# Analog_Greippi.net
KiCad netlist of a schematic drawn in EAGLE
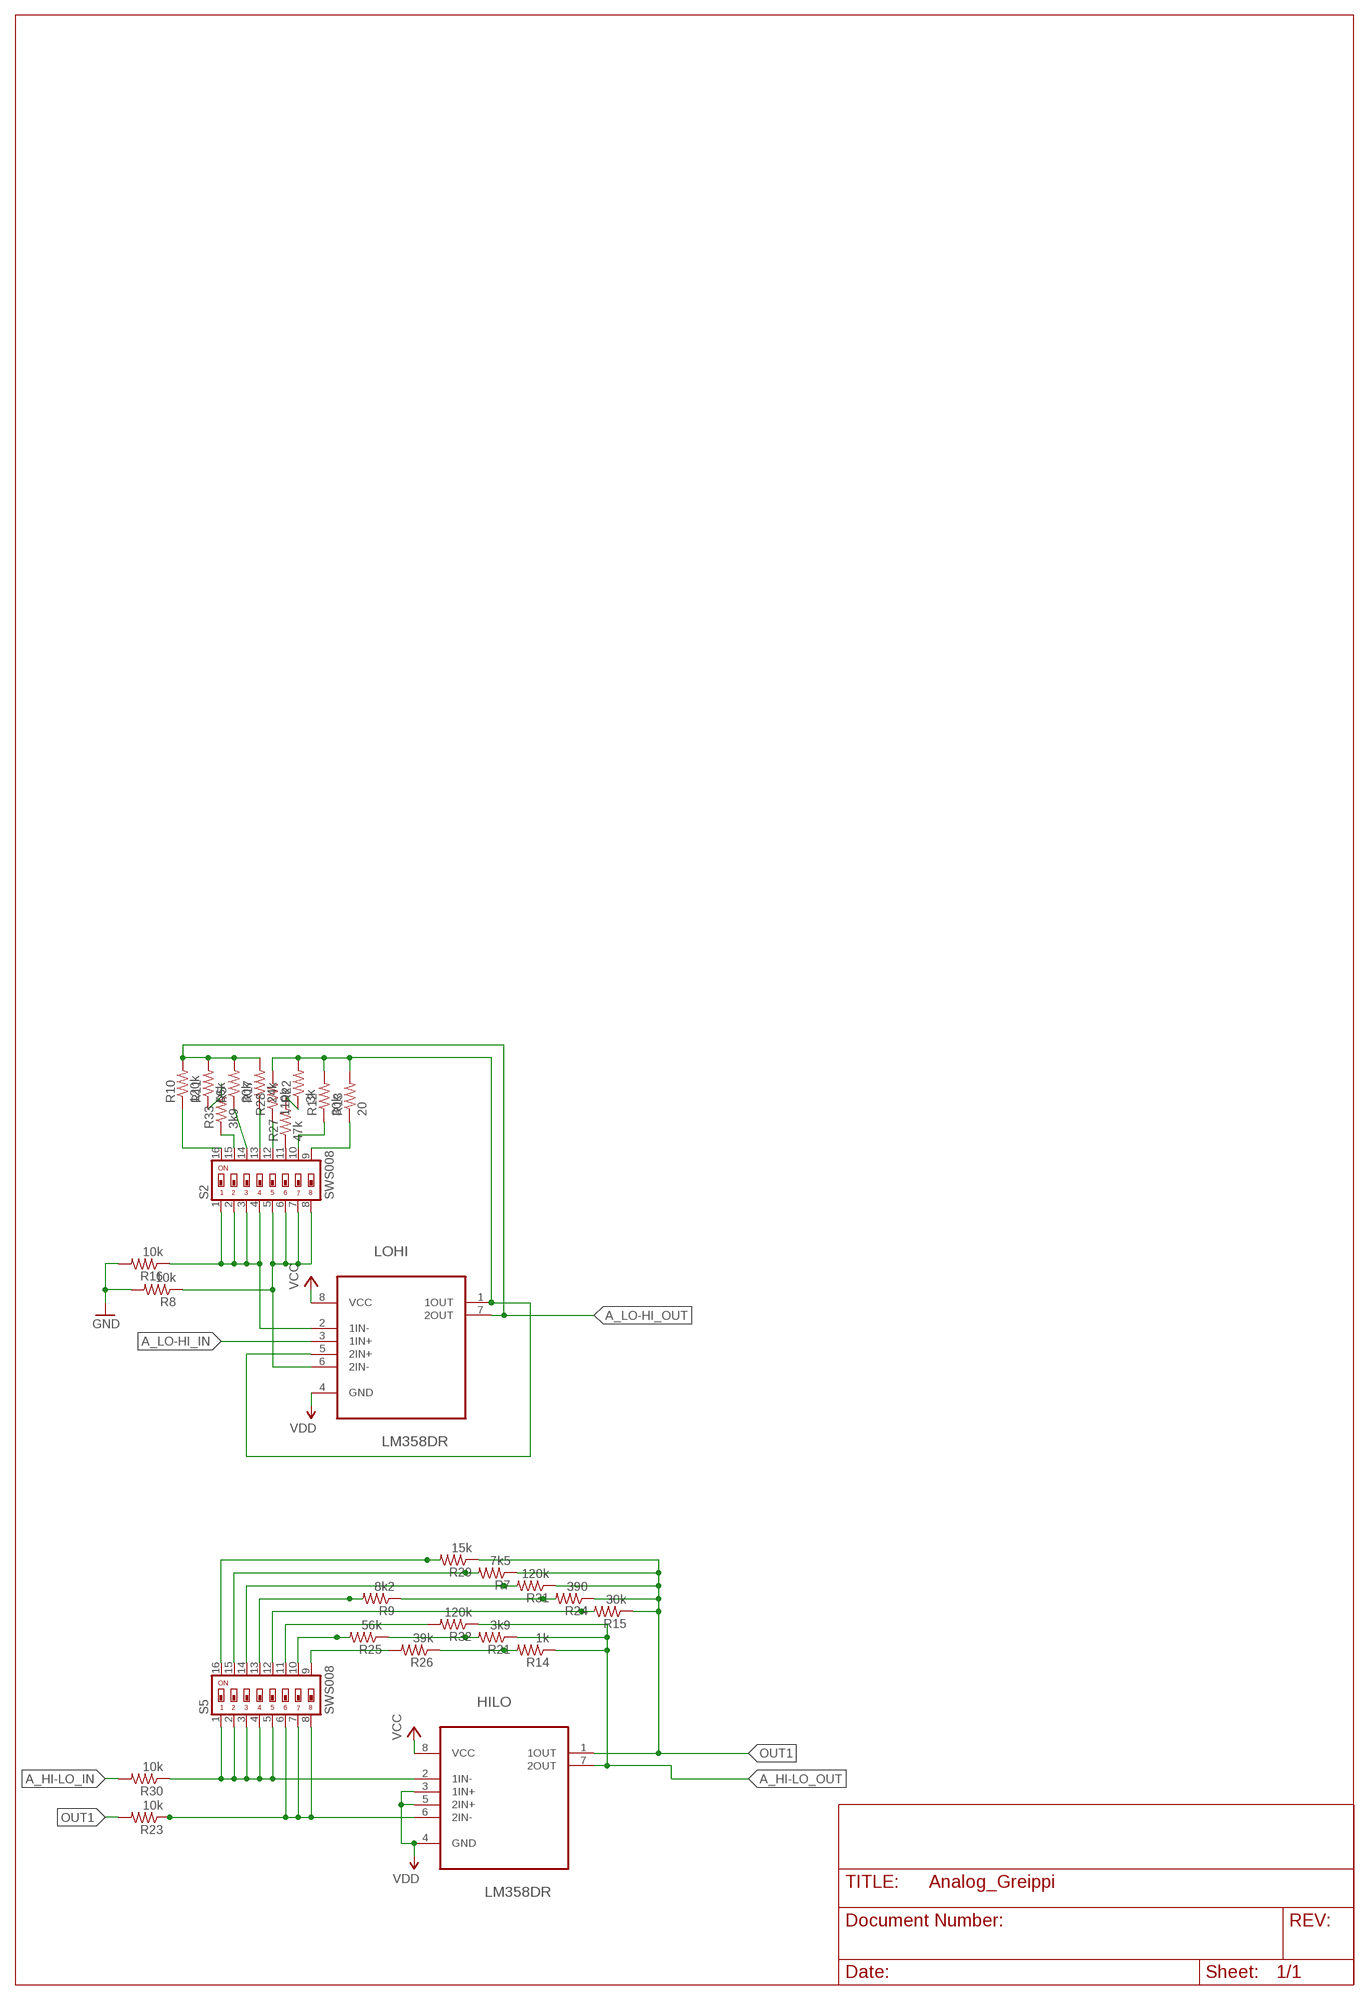
[diagram p0: schematic, sheet 1]

(export (version "E")
  (design (tool "Eeschema 10.0.6"))
  (components
    (comp (ref "HILO")
      (value "LM358DR")
      (footprint "eagle-import:SOIC127P600X175-8N")
      (libsource (lib "eagle-import") (part "LM358DR"))
    )
    (comp (ref "LOHI")
      (value "LM358DR")
      (footprint "eagle-import:SOIC127P600X175-8N")
      (libsource (lib "eagle-import") (part "LM358DR"))
    )
    (comp (ref "R5")
      (value "30k")
      (footprint "eagle-import:R0805")
      (libsource (lib "eagle-import") (part "R-US_R0805"))
    )
    (comp (ref "R7")
      (value "7k5")
      (footprint "eagle-import:R0805")
      (libsource (lib "eagle-import") (part "R-US_R0805"))
    )
    (comp (ref "R8")
      (value "10k")
      (footprint "eagle-import:R0805")
      (libsource (lib "eagle-import") (part "R-US_R0805"))
    )
    (comp (ref "R9")
      (value "8k2")
      (footprint "eagle-import:R0805")
      (libsource (lib "eagle-import") (part "R-US_R0805"))
    )
    (comp (ref "R10")
      (value "120k")
      (footprint "eagle-import:R0805")
      (libsource (lib "eagle-import") (part "R-US_R0805"))
    )
    (comp (ref "R11")
      (value "56k")
      (footprint "eagle-import:R0805")
      (libsource (lib "eagle-import") (part "R-US_R0805"))
    )
    (comp (ref "R12")
      (value "30k")
      (footprint "eagle-import:R0805")
      (libsource (lib "eagle-import") (part "R-US_R0805"))
    )
    (comp (ref "R13")
      (value "20")
      (footprint "eagle-import:R0805")
      (libsource (lib "eagle-import") (part "R-US_R0805"))
    )
    (comp (ref "R14")
      (value "1k")
      (footprint "eagle-import:R0805")
      (libsource (lib "eagle-import") (part "R-US_R0805"))
    )
    (comp (ref "R15")
      (value "30k")
      (footprint "eagle-import:R0805")
      (libsource (lib "eagle-import") (part "R-US_R0805"))
    )
    (comp (ref "R16")
      (value "10k")
      (footprint "eagle-import:R0805")
      (libsource (lib "eagle-import") (part "R-US_R0805"))
    )
    (comp (ref "R17")
      (value "24k")
      (footprint "eagle-import:R0805")
      (libsource (lib "eagle-import") (part "R-US_R0805"))
    )
    (comp (ref "R21")
      (value "3k9")
      (footprint "eagle-import:R0805")
      (libsource (lib "eagle-import") (part "R-US_R0805"))
    )
    (comp (ref "R22")
      (value "3k")
      (footprint "eagle-import:R0805")
      (libsource (lib "eagle-import") (part "R-US_R0805"))
    )
    (comp (ref "R23")
      (value "10k")
      (footprint "eagle-import:R0805")
      (libsource (lib "eagle-import") (part "R-US_R0805"))
    )
    (comp (ref "R24")
      (value "390")
      (footprint "eagle-import:R0805")
      (libsource (lib "eagle-import") (part "R-US_R0805"))
    )
    (comp (ref "R25")
      (value "56k")
      (footprint "eagle-import:R0805")
      (libsource (lib "eagle-import") (part "R-US_R0805"))
    )
    (comp (ref "R26")
      (value "39k")
      (footprint "eagle-import:R0805")
      (libsource (lib "eagle-import") (part "R-US_R0805"))
    )
    (comp (ref "R27")
      (value "47k")
      (footprint "eagle-import:R0805")
      (libsource (lib "eagle-import") (part "R-US_R0805"))
    )
    (comp (ref "R28")
      (value "110k")
      (footprint "eagle-import:R0805")
      (libsource (lib "eagle-import") (part "R-US_R0805"))
    )
    (comp (ref "R29")
      (value "15k")
      (footprint "eagle-import:R0805")
      (libsource (lib "eagle-import") (part "R-US_R0805"))
    )
    (comp (ref "R30")
      (value "10k")
      (footprint "eagle-import:R0805")
      (libsource (lib "eagle-import") (part "R-US_R0805"))
    )
    (comp (ref "R31")
      (value "120k")
      (footprint "eagle-import:R0805")
      (libsource (lib "eagle-import") (part "R-US_R0805"))
    )
    (comp (ref "R32")
      (value "120k")
      (footprint "eagle-import:R0805")
      (libsource (lib "eagle-import") (part "R-US_R0805"))
    )
    (comp (ref "R33")
      (value "3k9")
      (footprint "eagle-import:R0805")
      (libsource (lib "eagle-import") (part "R-US_R0805"))
    )
    (comp (ref "S2")
      (value "SWS008")
      (footprint "eagle-import:SMS-008")
      (libsource (lib "eagle-import") (part "SWS008"))
    )
    (comp (ref "S5")
      (value "SWS008")
      (footprint "eagle-import:SMS-008")
      (libsource (lib "eagle-import") (part "SWS008"))
    )
  )
  (nets
    (net (code "1") (name "A_HI-LO_IN") (class "Default")
      (node (ref "R30") (pin "2") (pinfunction "2_2") (pintype "passive"))
    )
    (net (code "2") (name "A_HI-LO_OUT") (class "Default")
      (node (ref "HILO") (pin "7") (pinfunction "2OUT_7") (pintype "output"))
      (node (ref "R14") (pin "1") (pinfunction "1_1") (pintype "passive"))
      (node (ref "R21") (pin "1") (pinfunction "1_1") (pintype "passive"))
      (node (ref "R32") (pin "1") (pinfunction "1_1") (pintype "passive"))
    )
    (net (code "3") (name "A_LO-HI_IN") (class "Default")
      (node (ref "LOHI") (pin "3") (pinfunction "1IN+_3") (pintype "input"))
    )
    (net (code "4") (name "A_LO-HI_OUT") (class "Default")
      (node (ref "LOHI") (pin "7") (pinfunction "2OUT_7") (pintype "output"))
      (node (ref "R10") (pin "2") (pinfunction "2_2") (pintype "passive"))
      (node (ref "R11") (pin "2") (pinfunction "2_2") (pintype "passive"))
      (node (ref "R17") (pin "2") (pinfunction "2_2") (pintype "passive"))
      (node (ref "R5") (pin "2") (pinfunction "2_2") (pintype "passive"))
    )
    (net (code "5") (name "GND") (class "Default")
      (node (ref "R16") (pin "2") (pinfunction "2_2") (pintype "passive"))
      (node (ref "R8") (pin "2") (pinfunction "2_2") (pintype "passive"))
    )
    (net (code "6") (name "Net-(HILO-1IN-)") (class "Default")
      (node (ref "HILO") (pin "2") (pinfunction "1IN-_2") (pintype "input"))
      (node (ref "R30") (pin "1") (pinfunction "1_1") (pintype "passive"))
      (node (ref "S5") (pin "1") (pinfunction "1_1") (pintype "passive"))
      (node (ref "S5") (pin "2") (pinfunction "2_2") (pintype "passive"))
      (node (ref "S5") (pin "3") (pinfunction "3_3") (pintype "passive"))
      (node (ref "S5") (pin "4") (pinfunction "4_4") (pintype "passive"))
      (node (ref "S5") (pin "5") (pinfunction "5_5") (pintype "passive"))
    )
    (net (code "7") (name "Net-(HILO-2IN-)") (class "Default")
      (node (ref "HILO") (pin "6") (pinfunction "2IN-_6") (pintype "input"))
      (node (ref "R23") (pin "1") (pinfunction "1_1") (pintype "passive"))
      (node (ref "S5") (pin "6") (pinfunction "6_6") (pintype "passive"))
      (node (ref "S5") (pin "7") (pinfunction "7_7") (pintype "passive"))
      (node (ref "S5") (pin "8") (pinfunction "8_8") (pintype "passive"))
    )
    (net (code "8") (name "Net-(LOHI-1IN-)") (class "Default")
      (node (ref "LOHI") (pin "2") (pinfunction "1IN-_2") (pintype "input"))
      (node (ref "R16") (pin "1") (pinfunction "1_1") (pintype "passive"))
      (node (ref "S2") (pin "1") (pinfunction "1_1") (pintype "passive"))
      (node (ref "S2") (pin "2") (pinfunction "2_2") (pintype "passive"))
      (node (ref "S2") (pin "3") (pinfunction "3_3") (pintype "passive"))
      (node (ref "S2") (pin "4") (pinfunction "4_4") (pintype "passive"))
    )
    (net (code "9") (name "Net-(LOHI-1OUT)") (class "Default")
      (node (ref "LOHI") (pin "1") (pinfunction "1OUT_1") (pintype "output"))
      (node (ref "LOHI") (pin "5") (pinfunction "2IN+_5") (pintype "input"))
      (node (ref "R12") (pin "2") (pinfunction "2_2") (pintype "passive"))
      (node (ref "R13") (pin "2") (pinfunction "2_2") (pintype "passive"))
      (node (ref "R22") (pin "2") (pinfunction "2_2") (pintype "passive"))
      (node (ref "R28") (pin "2") (pinfunction "2_2") (pintype "passive"))
    )
    (net (code "10") (name "Net-(LOHI-2IN-)") (class "Default")
      (node (ref "LOHI") (pin "6") (pinfunction "2IN-_6") (pintype "input"))
      (node (ref "R8") (pin "1") (pinfunction "1_1") (pintype "passive"))
      (node (ref "S2") (pin "5") (pinfunction "5_5") (pintype "passive"))
      (node (ref "S2") (pin "6") (pinfunction "6_6") (pintype "passive"))
      (node (ref "S2") (pin "7") (pinfunction "7_7") (pintype "passive"))
      (node (ref "S2") (pin "8") (pinfunction "8_8") (pintype "passive"))
    )
    (net (code "11") (name "Net-(R5-Pad1)") (class "Default")
      (node (ref "R5") (pin "1") (pinfunction "1_1") (pintype "passive"))
      (node (ref "S2") (pin "14") (pinfunction "14_14") (pintype "passive"))
    )
    (net (code "12") (name "Net-(R7-Pad2)") (class "Default")
      (node (ref "R7") (pin "2") (pinfunction "2_2") (pintype "passive"))
      (node (ref "S5") (pin "15") (pinfunction "15_15") (pintype "passive"))
    )
    (net (code "13") (name "Net-(R9-Pad2)") (class "Default")
      (node (ref "R9") (pin "2") (pinfunction "2_2") (pintype "passive"))
      (node (ref "S5") (pin "13") (pinfunction "13_13") (pintype "passive"))
    )
    (net (code "14") (name "Net-(R10-Pad1)") (class "Default")
      (node (ref "R10") (pin "1") (pinfunction "1_1") (pintype "passive"))
      (node (ref "S2") (pin "16") (pinfunction "16_16") (pintype "passive"))
    )
    (net (code "15") (name "Net-(R11-Pad1)") (class "Default")
      (node (ref "R11") (pin "1") (pinfunction "1_1") (pintype "passive"))
      (node (ref "R33") (pin "2") (pinfunction "2_2") (pintype "passive"))
    )
    (net (code "16") (name "Net-(R12-Pad1)") (class "Default")
      (node (ref "R12") (pin "1") (pinfunction "1_1") (pintype "passive"))
      (node (ref "S2") (pin "10") (pinfunction "10_10") (pintype "passive"))
    )
    (net (code "17") (name "Net-(R13-Pad1)") (class "Default")
      (node (ref "R13") (pin "1") (pinfunction "1_1") (pintype "passive"))
      (node (ref "S2") (pin "9") (pinfunction "9_9") (pintype "passive"))
    )
    (net (code "18") (name "Net-(R14-Pad2)") (class "Default")
      (node (ref "R14") (pin "2") (pinfunction "2_2") (pintype "passive"))
      (node (ref "R26") (pin "1") (pinfunction "1_1") (pintype "passive"))
    )
    (net (code "19") (name "Net-(R15-Pad2)") (class "Default")
      (node (ref "R15") (pin "2") (pinfunction "2_2") (pintype "passive"))
      (node (ref "S5") (pin "12") (pinfunction "12_12") (pintype "passive"))
    )
    (net (code "20") (name "Net-(R17-Pad1)") (class "Default")
      (node (ref "R17") (pin "1") (pinfunction "1_1") (pintype "passive"))
      (node (ref "S2") (pin "13") (pinfunction "13_13") (pintype "passive"))
    )
    (net (code "21") (name "Net-(R21-Pad2)") (class "Default")
      (node (ref "R21") (pin "2") (pinfunction "2_2") (pintype "passive"))
      (node (ref "R25") (pin "1") (pinfunction "1_1") (pintype "passive"))
    )
    (net (code "22") (name "Net-(R22-Pad1)") (class "Default")
      (node (ref "R22") (pin "1") (pinfunction "1_1") (pintype "passive"))
      (node (ref "R27") (pin "2") (pinfunction "2_2") (pintype "passive"))
    )
    (net (code "23") (name "Net-(R24-Pad2)") (class "Default")
      (node (ref "R24") (pin "2") (pinfunction "2_2") (pintype "passive"))
      (node (ref "R9") (pin "1") (pinfunction "1_1") (pintype "passive"))
    )
    (net (code "24") (name "Net-(R25-Pad2)") (class "Default")
      (node (ref "R25") (pin "2") (pinfunction "2_2") (pintype "passive"))
      (node (ref "S5") (pin "10") (pinfunction "10_10") (pintype "passive"))
    )
    (net (code "25") (name "Net-(R26-Pad2)") (class "Default")
      (node (ref "R26") (pin "2") (pinfunction "2_2") (pintype "passive"))
      (node (ref "S5") (pin "9") (pinfunction "9_9") (pintype "passive"))
    )
    (net (code "26") (name "Net-(R27-Pad1)") (class "Default")
      (node (ref "R27") (pin "1") (pinfunction "1_1") (pintype "passive"))
      (node (ref "S2") (pin "11") (pinfunction "11_11") (pintype "passive"))
    )
    (net (code "27") (name "Net-(R28-Pad1)") (class "Default")
      (node (ref "R28") (pin "1") (pinfunction "1_1") (pintype "passive"))
      (node (ref "S2") (pin "12") (pinfunction "12_12") (pintype "passive"))
    )
    (net (code "28") (name "Net-(R29-Pad2)") (class "Default")
      (node (ref "R29") (pin "2") (pinfunction "2_2") (pintype "passive"))
      (node (ref "S5") (pin "16") (pinfunction "16_16") (pintype "passive"))
    )
    (net (code "29") (name "Net-(R31-Pad2)") (class "Default")
      (node (ref "R31") (pin "2") (pinfunction "2_2") (pintype "passive"))
      (node (ref "S5") (pin "14") (pinfunction "14_14") (pintype "passive"))
    )
    (net (code "30") (name "Net-(R32-Pad2)") (class "Default")
      (node (ref "R32") (pin "2") (pinfunction "2_2") (pintype "passive"))
      (node (ref "S5") (pin "11") (pinfunction "11_11") (pintype "passive"))
    )
    (net (code "31") (name "Net-(R33-Pad1)") (class "Default")
      (node (ref "R33") (pin "1") (pinfunction "1_1") (pintype "passive"))
      (node (ref "S2") (pin "15") (pinfunction "15_15") (pintype "passive"))
    )
    (net (code "32") (name "OUT1") (class "Default")
      (node (ref "HILO") (pin "1") (pinfunction "1OUT_1") (pintype "output"))
      (node (ref "R15") (pin "1") (pinfunction "1_1") (pintype "passive"))
      (node (ref "R23") (pin "2") (pinfunction "2_2") (pintype "passive"))
      (node (ref "R24") (pin "1") (pinfunction "1_1") (pintype "passive"))
      (node (ref "R29") (pin "1") (pinfunction "1_1") (pintype "passive"))
      (node (ref "R31") (pin "1") (pinfunction "1_1") (pintype "passive"))
      (node (ref "R7") (pin "1") (pinfunction "1_1") (pintype "passive"))
    )
    (net (code "33") (name "VCC") (class "Default")
      (node (ref "HILO") (pin "8") (pinfunction "VCC_8") (pintype "power_in"))
      (node (ref "LOHI") (pin "8") (pinfunction "VCC_8") (pintype "power_in"))
    )
    (net (code "34") (name "VDD") (class "Default")
      (node (ref "HILO") (pin "3") (pinfunction "1IN+_3") (pintype "input"))
      (node (ref "HILO") (pin "4") (pinfunction "GND_4") (pintype "passive"))
      (node (ref "HILO") (pin "5") (pinfunction "2IN+_5") (pintype "input"))
      (node (ref "LOHI") (pin "4") (pinfunction "GND_4") (pintype "passive"))
    )
  )
)
